# wifi-plug.net
KiCad netlist of a schematic drawn in Altium Designer
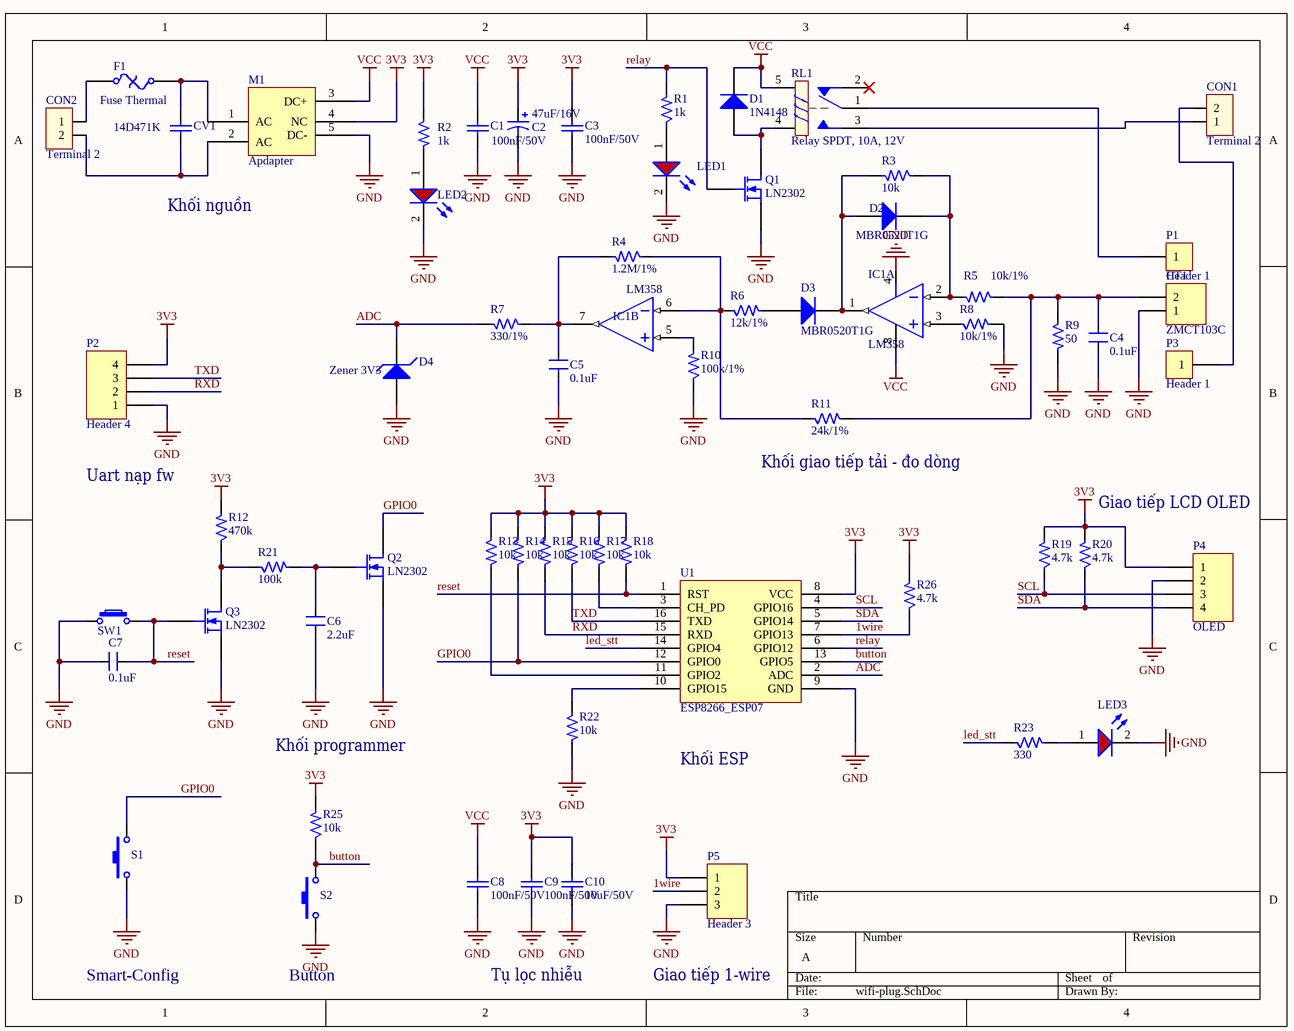
[diagram p0: wifi-plug.SchDoc]

(export (version "E")
  (design (tool "Eeschema 10.0.6"))
  (components
    (comp (ref "C1")
      (value "100nF/50V")
      (footprint "C0805")
      (description "Capacitor 100n 16V 0603")
      (fields (field (name "PUBLISHER") "Altium Limited"))
      (libsource (lib "Capacitor") (part "Cap Semi"))
    )
    (comp (ref "C2")
      (value "47uF/16V")
      (footprint "C2312")
      (description "Polarized Capacitor (Surface Mount)")
      (fields (field (name "PUBLISHER") "Altium Limited"))
      (libsource (lib "Miscellaneous Devices") (part "Cap Pol3"))
    )
    (comp (ref "C3")
      (value "100nF/50V")
      (footprint "C0805")
      (description "Capacitor 100n 16V 0603")
      (fields (field (name "PUBLISHER") "Altium Limited"))
      (libsource (lib "Capacitor") (part "Cap Semi"))
    )
    (comp (ref "C4")
      (value "0.1uF")
      (footprint "C0805")
      (description "SMD Ceramic  Capacitor")
      (fields (field (name "VOLTAGE") "50V") (field (name "TOLERANCE") "10%"))
      (libsource (lib "ST") (part "CM Ceramic"))
    )
    (comp (ref "C5")
      (value "0.1uF")
      (footprint "C0805")
      (description "SMD Ceramic  Capacitor")
      (fields (field (name "VOLTAGE") "50V") (field (name "TOLERANCE") "10%"))
      (libsource (lib "ST") (part "CM Ceramic"))
    )
    (comp (ref "C6")
      (value "2.2uF")
      (footprint "C0805")
      (description "SMD Ceramic  Capacitor")
      (fields (field (name "VOLTAGE") "50V") (field (name "TOLERANCE") "10%"))
      (libsource (lib "ST") (part "CM Ceramic"))
    )
    (comp (ref "C7")
      (value "0.1uF")
      (footprint "C0805")
      (description "SMD Ceramic  Capacitor")
      (fields (field (name "VOLTAGE") "50V") (field (name "TOLERANCE") "10%"))
      (libsource (lib "ST") (part "CM Ceramic"))
    )
    (comp (ref "C8")
      (value "100nF/50V")
      (footprint "C0805")
      (description "Capacitor 100n 16V 0603")
      (fields (field (name "PUBLISHER") "Altium Limited"))
      (libsource (lib "Capacitor") (part "Cap Semi"))
    )
    (comp (ref "C9")
      (value "100nF/50V")
      (footprint "C0805")
      (description "Capacitor 100n 16V 0603")
      (fields (field (name "PUBLISHER") "Altium Limited"))
      (libsource (lib "Capacitor") (part "Cap Semi"))
    )
    (comp (ref "C10")
      (value "10uF/50V")
      (footprint "C1206")
      (description "Capacitor 100n 16V 0603")
      (fields (field (name "PUBLISHER") "Altium Limited"))
      (libsource (lib "Capacitor") (part "Cap Semi"))
    )
    (comp (ref "CON1")
      (value "Terminal 2")
      (footprint "domino-2pin-7.62")
      (libsource (lib "") (part "Terminal 2_1"))
    )
    (comp (ref "CON2")
      (value "Terminal 2")
      (footprint "domino-2pin-7.62")
      (libsource (lib "SS_Con") (part "Terminal 2"))
    )
    (comp (ref "CT1")
      (value "ZMCT103C")
      (footprint "ZMCT103C")
      (description "Header, 2-Pin")
      (fields (field (name "PUBLISHER") "Altium Limited"))
      (libsource (lib "SS_Con") (part "Header 2"))
    )
    (comp (ref "CV1")
      (value "14D471K")
      (footprint "C_Ceramic_KV")
      (description "Polar Capacitor")
      (fields (field (name "Comment") "Cap1") (field (name "PUBLISHER") "Altium Limited"))
      (libsource (lib "SS_Basic") (part "Cap1"))
    )
    (comp (ref "D1")
      (value "1N4148")
      (footprint "DO-214AC (SMA)")
      (description "Diode Normal")
      (fields (field (name "PUBLISHER") "Altium Limited"))
      (libsource (lib "Schematic") (part "Diode Normal"))
    )
    (comp (ref "D2")
      (value "MBR0520T1G")
      (footprint "SOD-123 W")
      (description "Diode Normal")
      (fields (field (name "PUBLISHER") "Altium Limited"))
      (libsource (lib "Schematic") (part "Diode Normal"))
    )
    (comp (ref "D3")
      (value "MBR0520T1G")
      (footprint "SOD-123 W")
      (description "Diode Normal")
      (fields (field (name "PUBLISHER") "Altium Limited"))
      (libsource (lib "Schematic") (part "Diode Normal"))
    )
    (comp (ref "D4")
      (value "Zener 3V3")
      (footprint "SOD-123")
      (description "Zener Voltage Regulators")
      (fields (field (name "MANUFACTURER") "ON Semiconductor"))
      (libsource (lib "ST") (part "Diode Zener"))
    )
    (comp (ref "F1")
      (value "Fuse Thermal")
      (footprint "PTC1812")
      (description "Thermal Fuse")
      (fields (field (name "PUBLISHER") "Altium Limited"))
      (libsource (lib "Miscellaneous Devices") (part "Fuse Thermal"))
    )
    (comp (ref "IC1")
      (value "LM358")
      (footprint "SOIC8")
      (description "Low-Power Dual Operational Amplifier")
      (libsource (lib "ST") (part "LM358"))
    )
    (comp (ref "LED1")
      (value "150080RS75000")
      (footprint "led-3mm")
      (description "SMD mono-color Chip LED, WL-SMCW, Red")
      (fields
        (field (name "MANUFACTURER") "W黵th Elektronik eiSos GmbH")
        (field (name "CREATED BY") "Christin Otto")
      )
      (libsource (lib "led-lib") (part "led-0805"))
    )
    (comp (ref "LED2")
      (value "150080RS75000")
      (footprint "LED_0805_Red")
      (description "SMD mono-color Chip LED, WL-SMCW, Red")
      (fields
        (field (name "MANUFACTURER") "W黵th Elektronik eiSos GmbH")
        (field (name "CREATED BY") "Christin Otto")
      )
      (libsource (lib "led-lib") (part "led-0805"))
    )
    (comp (ref "LED3")
      (value "150080RS75000")
      (footprint "led-lib:led-3mm")
      (description "SMD mono-color Chip LED, WL-SMCW, Red")
      (fields
        (field (name "MANUFACTURER") "W黵th Elektronik eiSos GmbH")
        (field (name "CREATED BY") "Christin Otto")
      )
      (libsource (lib "led-lib") (part "led-0805"))
    )
    (comp (ref "M1")
      (value "Apdapter")
      (footprint "Module-Supply")
      (libsource (lib "SS_Module") (part "Module_Supply"))
    )
    (comp (ref "P1")
      (value "Header 1")
      (footprint "PAD 1")
      (description "Header, 1-Pin")
      (fields (field (name "PUBLISHER") "Altium Limited"))
      (libsource (lib "") (part "Header 1_1"))
    )
    (comp (ref "P2")
      (value "Header 4")
      (footprint "SS_Con:HDR1X4H")
      (description "Header, 4-Pin")
      (fields (field (name "PUBLISHER") "Altium Limited"))
      (libsource (lib "SS_Con") (part "Header 4"))
    )
    (comp (ref "P3")
      (value "Header 1")
      (footprint "PAD 1")
      (description "Header, 1-Pin")
      (fields (field (name "PUBLISHER") "Altium Limited"))
      (libsource (lib "SS_Con") (part "Header 1"))
    )
    (comp (ref "P4")
      (value "OLED")
      (footprint "SS_Con:HDR1X4 - FEMALE")
      (description "Header, 4-Pin")
      (fields (field (name "PUBLISHER") "Altium Limited"))
      (libsource (lib "") (part "Header 4_1"))
    )
    (comp (ref "P5")
      (value "Header 3")
      (footprint "SS_Con:HDR1X3")
      (description "Header, 3-Pin")
      (fields (field (name "PUBLISHER") "Altium Limited"))
      (libsource (lib "SS_Con") (part "Header 3"))
    )
    (comp (ref "Q1")
      (value "LN2302")
      (footprint "PcbLib1:SOT23-3")
      (description "N-Channel MOSFET")
      (fields (field (name "PUBLISHER") "Altium Limited"))
      (libsource (lib "Schlib2") (part "MOSFET-N"))
    )
    (comp (ref "Q2")
      (value "LN2302")
      (footprint "SOT23-3")
      (description "N-Channel MOSFET")
      (fields (field (name "PUBLISHER") "Altium Limited"))
      (libsource (lib "Schlib2") (part "MOSFET-N"))
    )
    (comp (ref "Q3")
      (value "LN2302")
      (footprint "SOT23-3")
      (description "N-Channel MOSFET")
      (fields (field (name "PUBLISHER") "Altium Limited"))
      (libsource (lib "Schlib2") (part "MOSFET-N"))
    )
    (comp (ref "R1")
      (value "1k")
      (footprint "R0805")
      (description "Resistor SMD")
      (fields (field (name "MANUFACTURER") "UniOhm"))
      (libsource (lib "ST") (part "RM"))
    )
    (comp (ref "R2")
      (value "1k")
      (footprint "R0805")
      (description "Resistor SMD")
      (fields (field (name "MANUFACTURER") "UniOhm"))
      (libsource (lib "ST") (part "RM"))
    )
    (comp (ref "R3")
      (value "10k")
      (footprint "R0805")
      (description "Resistor SMD")
      (fields (field (name "MANUFACTURER") "UniOhm"))
      (libsource (lib "ST") (part "RM"))
    )
    (comp (ref "R4")
      (value "1.2M/1%")
      (footprint "R0805")
      (description "Resistor SMD")
      (fields (field (name "MANUFACTURER") "UniOhm"))
      (libsource (lib "ST") (part "RM"))
    )
    (comp (ref "R5")
      (value "10k/1%")
      (footprint "R0805")
      (description "Resistor SMD")
      (fields (field (name "MANUFACTURER") "UniOhm"))
      (libsource (lib "ST") (part "RM"))
    )
    (comp (ref "R6")
      (value "12k/1%")
      (footprint "R0805")
      (description "Resistor SMD")
      (fields (field (name "MANUFACTURER") "UniOhm"))
      (libsource (lib "ST") (part "RM"))
    )
    (comp (ref "R7")
      (value "330/1%")
      (footprint "R0805")
      (description "Resistor SMD")
      (fields (field (name "MANUFACTURER") "UniOhm"))
      (libsource (lib "ST") (part "RM"))
    )
    (comp (ref "R8")
      (value "10k/1%")
      (footprint "R0805")
      (description "Resistor SMD")
      (fields (field (name "MANUFACTURER") "UniOhm"))
      (libsource (lib "ST") (part "RM"))
    )
    (comp (ref "R9")
      (value "50")
      (footprint "R0805")
      (description "Resistor SMD")
      (fields (field (name "MANUFACTURER") "UniOhm"))
      (libsource (lib "ST") (part "RM"))
    )
    (comp (ref "R10")
      (value "100k/1%")
      (footprint "R0805")
      (description "Resistor SMD")
      (fields (field (name "MANUFACTURER") "UniOhm"))
      (libsource (lib "ST") (part "RM"))
    )
    (comp (ref "R11")
      (value "24k/1%")
      (footprint "R0805")
      (description "Resistor SMD")
      (fields (field (name "MANUFACTURER") "UniOhm"))
      (libsource (lib "ST") (part "RM"))
    )
    (comp (ref "R12")
      (value "470k")
      (footprint "R0805")
      (description "Resistor SMD")
      (fields (field (name "MANUFACTURER") "UniOhm"))
      (libsource (lib "ST") (part "RM"))
    )
    (comp (ref "R13")
      (value "10k")
      (footprint "R0805")
      (description "Resistor SMD")
      (fields (field (name "MANUFACTURER") "UniOhm"))
      (libsource (lib "ST") (part "RM"))
    )
    (comp (ref "R14")
      (value "10k")
      (footprint "R0805")
      (description "Resistor SMD")
      (fields (field (name "MANUFACTURER") "UniOhm"))
      (libsource (lib "ST") (part "RM"))
    )
    (comp (ref "R15")
      (value "10k")
      (footprint "R0805")
      (description "Resistor SMD")
      (fields (field (name "MANUFACTURER") "UniOhm"))
      (libsource (lib "ST") (part "RM"))
    )
    (comp (ref "R16")
      (value "10k")
      (footprint "R0805")
      (description "Resistor SMD")
      (fields (field (name "MANUFACTURER") "UniOhm"))
      (libsource (lib "ST") (part "RM"))
    )
    (comp (ref "R17")
      (value "10k")
      (footprint "R0805")
      (description "Resistor SMD")
      (fields (field (name "MANUFACTURER") "UniOhm"))
      (libsource (lib "ST") (part "RM"))
    )
    (comp (ref "R18")
      (value "10k")
      (footprint "R0805")
      (description "Resistor SMD")
      (fields (field (name "MANUFACTURER") "UniOhm"))
      (libsource (lib "ST") (part "RM"))
    )
    (comp (ref "R19")
      (value "4.7k")
      (footprint "R0805")
      (description "Resistor SMD")
      (fields (field (name "MANUFACTURER") "UniOhm"))
      (libsource (lib "ST") (part "RM"))
    )
    (comp (ref "R20")
      (value "4.7k")
      (footprint "R0805")
      (description "Resistor SMD")
      (fields (field (name "MANUFACTURER") "UniOhm"))
      (libsource (lib "ST") (part "RM"))
    )
    (comp (ref "R21")
      (value "100k")
      (footprint "R0805")
      (description "Resistor SMD")
      (fields (field (name "MANUFACTURER") "UniOhm"))
      (libsource (lib "ST") (part "RM"))
    )
    (comp (ref "R22")
      (value "10k")
      (footprint "R0805")
      (description "Resistor SMD")
      (fields (field (name "MANUFACTURER") "UniOhm"))
      (libsource (lib "ST") (part "RM"))
    )
    (comp (ref "R23")
      (value "330")
      (footprint "R0805")
      (description "Resistor SMD")
      (fields (field (name "MANUFACTURER") "UniOhm"))
      (libsource (lib "ST") (part "RM"))
    )
    (comp (ref "R25")
      (value "10k")
      (footprint "R0805")
      (description "Resistor SMD")
      (fields (field (name "MANUFACTURER") "UniOhm"))
      (libsource (lib "ST") (part "RM"))
    )
    (comp (ref "R26")
      (value "4.7k")
      (footprint "R0805")
      (description "Resistor SMD")
      (fields (field (name "MANUFACTURER") "UniOhm"))
      (libsource (lib "ST") (part "RM"))
    )
    (comp (ref "RL1")
      (value "Relay SPDT, 10A, 12V")
      (footprint "RL_SPDT_10A")
      (description "Relay SPDT,10A - 12VDC 5 Pin")
      (libsource (lib "nhantt-relay-lib") (part "Relay 1"))
    )
    (comp (ref "S1")
      (value "SW-SMD")
      (footprint "Button Tactile Switch")
      (description "Switch")
      (fields (field (name "PUBLISHER") "Altium Limited"))
      (libsource (lib "Schematic") (part "SW-SMD"))
    )
    (comp (ref "S2")
      (value "SW-SMD")
      (footprint "Button Tactile Switch")
      (description "Switch")
      (fields (field (name "PUBLISHER") "Altium Limited"))
      (libsource (lib "Schematic") (part "SW-SMD"))
    )
    (comp (ref "SW1") (value "SW2") (footprint "SMD(2)") (libsource (lib "SC") (part "SW2")))
    (comp (ref "U1")
      (value "ESP8266_ESP07")
      (footprint "ESP_12")
      (libsource (lib "STMicroelectronics") (part "ESP8266_ESP07"))
    )
  )
  (nets
    (net (code "1") (name "/1wire") (class "Default")
      (node (ref "P5") (pin "2") (pinfunction "2_2") (pintype "passive"))
      (node (ref "R26") (pin "1") (pinfunction "1_1") (pintype "passive"))
      (node (ref "U1") (pin "7") (pinfunction "GPIO13_7") (pintype "passive"))
    )
    (net (code "2") (name "/ADC") (class "Default")
      (node (ref "D4") (pin "1") (pinfunction "K_1") (pintype "passive"))
      (node (ref "R7") (pin "2") (pinfunction "2_2") (pintype "passive"))
      (node (ref "U1") (pin "2") (pinfunction "ADC_2") (pintype "passive"))
    )
    (net (code "3") (name "/GPIO0") (class "Default")
      (node (ref "Q2") (pin "3") (pinfunction "D_3") (pintype "passive"))
      (node (ref "R14") (pin "2") (pinfunction "2_2") (pintype "passive"))
      (node (ref "S1") (pin "2") (pinfunction "2_2") (pintype "passive"))
      (node (ref "U1") (pin "12") (pinfunction "GPIO0_12") (pintype "passive"))
    )
    (net (code "4") (name "/RXD") (class "Default")
      (node (ref "P2") (pin "2") (pinfunction "2_2") (pintype "passive"))
      (node (ref "R15") (pin "2") (pinfunction "2_2") (pintype "passive"))
      (node (ref "U1") (pin "15") (pinfunction "RXD_15") (pintype "passive"))
    )
    (net (code "5") (name "/SCL") (class "Default")
      (node (ref "P4") (pin "3") (pinfunction "3_3") (pintype "passive"))
      (node (ref "R19") (pin "1") (pinfunction "1_1") (pintype "passive"))
      (node (ref "U1") (pin "4") (pinfunction "GPIO16_4") (pintype "passive"))
    )
    (net (code "6") (name "/SDA") (class "Default")
      (node (ref "P4") (pin "4") (pinfunction "4_4") (pintype "passive"))
      (node (ref "R20") (pin "1") (pinfunction "1_1") (pintype "passive"))
      (node (ref "U1") (pin "5") (pinfunction "GPIO14_5") (pintype "passive"))
    )
    (net (code "7") (name "/TXD") (class "Default")
      (node (ref "P2") (pin "3") (pinfunction "3_3") (pintype "passive"))
      (node (ref "R16") (pin "2") (pinfunction "2_2") (pintype "passive"))
      (node (ref "U1") (pin "16") (pinfunction "TXD_16") (pintype "passive"))
    )
    (net (code "8") (name "/button") (class "Default")
      (node (ref "R25") (pin "1") (pinfunction "1_1") (pintype "passive"))
      (node (ref "S2") (pin "2") (pinfunction "2_2") (pintype "passive"))
      (node (ref "U1") (pin "13") (pinfunction "GPIO5_13") (pintype "passive"))
    )
    (net (code "9") (name "/led_stt") (class "Default")
      (node (ref "R23") (pin "1") (pinfunction "1_1") (pintype "passive"))
      (node (ref "U1") (pin "14") (pinfunction "GPIO4_14") (pintype "passive"))
    )
    (net (code "10") (name "/relay") (class "Default")
      (node (ref "Q1") (pin "1") (pinfunction "G_1") (pintype "passive"))
      (node (ref "R1") (pin "2") (pinfunction "2_2") (pintype "passive"))
      (node (ref "U1") (pin "6") (pinfunction "GPIO12_6") (pintype "passive"))
    )
    (net (code "11") (name "/reset") (class "Default")
      (node (ref "C7") (pin "2") (pinfunction "2_2") (pintype "passive"))
      (node (ref "Q3") (pin "1") (pinfunction "G_1") (pintype "passive"))
      (node (ref "R18") (pin "2") (pinfunction "2_2") (pintype "passive"))
      (node (ref "SW1") (pin "2") (pinfunction "2_2") (pintype "passive"))
      (node (ref "U1") (pin "1") (pinfunction "RST_1") (pintype "passive"))
    )
    (net (code "12") (name "3V3") (class "Default")
      (node (ref "C10") (pin "1") (pinfunction "1_1") (pintype "passive"))
      (node (ref "C2") (pin "1") (pinfunction "1_1") (pintype "passive"))
      (node (ref "C3") (pin "1") (pinfunction "1_1") (pintype "passive"))
      (node (ref "C9") (pin "1") (pinfunction "1_1") (pintype "passive"))
      (node (ref "M1") (pin "4") (pinfunction "NC_4") (pintype "passive"))
      (node (ref "P2") (pin "4") (pinfunction "4_4") (pintype "passive"))
      (node (ref "P4") (pin "1") (pinfunction "1_1") (pintype "passive"))
      (node (ref "P5") (pin "1") (pinfunction "1_1") (pintype "passive"))
      (node (ref "R12") (pin "2") (pinfunction "2_2") (pintype "passive"))
      (node (ref "R13") (pin "1") (pinfunction "1_1") (pintype "passive"))
      (node (ref "R14") (pin "1") (pinfunction "1_1") (pintype "passive"))
      (node (ref "R15") (pin "1") (pinfunction "1_1") (pintype "passive"))
      (node (ref "R16") (pin "1") (pinfunction "1_1") (pintype "passive"))
      (node (ref "R17") (pin "1") (pinfunction "1_1") (pintype "passive"))
      (node (ref "R18") (pin "1") (pinfunction "1_1") (pintype "passive"))
      (node (ref "R19") (pin "2") (pinfunction "2_2") (pintype "passive"))
      (node (ref "R2") (pin "1") (pinfunction "1_1") (pintype "passive"))
      (node (ref "R20") (pin "2") (pinfunction "2_2") (pintype "passive"))
      (node (ref "R25") (pin "2") (pinfunction "2_2") (pintype "passive"))
      (node (ref "R26") (pin "2") (pinfunction "2_2") (pintype "passive"))
      (node (ref "U1") (pin "8") (pinfunction "VCC_8") (pintype "passive"))
    )
    (net (code "13") (name "GND") (class "Default")
      (node (ref "C1") (pin "2") (pinfunction "2_2") (pintype "passive"))
      (node (ref "C10") (pin "2") (pinfunction "2_2") (pintype "passive"))
      (node (ref "C2") (pin "2") (pinfunction "2_2") (pintype "passive"))
      (node (ref "C3") (pin "2") (pinfunction "2_2") (pintype "passive"))
      (node (ref "C4") (pin "1") (pinfunction "1_1") (pintype "passive"))
      (node (ref "C5") (pin "1") (pinfunction "1_1") (pintype "passive"))
      (node (ref "C6") (pin "1") (pinfunction "1_1") (pintype "passive"))
      (node (ref "C7") (pin "1") (pinfunction "1_1") (pintype "passive"))
      (node (ref "C8") (pin "2") (pinfunction "2_2") (pintype "passive"))
      (node (ref "C9") (pin "2") (pinfunction "2_2") (pintype "passive"))
      (node (ref "CT1") (pin "1") (pinfunction "1_1") (pintype "passive"))
      (node (ref "D4") (pin "2") (pinfunction "A_2") (pintype "passive"))
      (node (ref "IC1") (pin "4") (pinfunction "-V_4") (pintype "passive"))
      (node (ref "LED1") (pin "2") (pinfunction "C_2") (pintype "passive"))
      (node (ref "LED2") (pin "2") (pinfunction "C_2") (pintype "passive"))
      (node (ref "LED3") (pin "2") (pinfunction "C_2") (pintype "passive"))
      (node (ref "M1") (pin "5") (pinfunction "DC-_5") (pintype "passive"))
      (node (ref "P2") (pin "1") (pinfunction "1_1") (pintype "passive"))
      (node (ref "P4") (pin "2") (pinfunction "2_2") (pintype "passive"))
      (node (ref "P5") (pin "3") (pinfunction "3_3") (pintype "passive"))
      (node (ref "Q1") (pin "2") (pinfunction "S_2") (pintype "passive"))
      (node (ref "Q2") (pin "2") (pinfunction "S_2") (pintype "passive"))
      (node (ref "Q3") (pin "2") (pinfunction "S_2") (pintype "passive"))
      (node (ref "R10") (pin "1") (pinfunction "1_1") (pintype "passive"))
      (node (ref "R22") (pin "2") (pinfunction "2_2") (pintype "passive"))
      (node (ref "R8") (pin "2") (pinfunction "2_2") (pintype "passive"))
      (node (ref "R9") (pin "2") (pinfunction "2_2") (pintype "passive"))
      (node (ref "S1") (pin "1") (pinfunction "1_1") (pintype "passive"))
      (node (ref "S2") (pin "1") (pinfunction "1_1") (pintype "passive"))
      (node (ref "SW1") (pin "1") (pinfunction "1_1") (pintype "passive"))
      (node (ref "U1") (pin "9") (pinfunction "GND_9") (pintype "passive"))
    )
    (net (code "14") (name "Net-(C4-Pad2)") (class "Default")
      (node (ref "C4") (pin "2") (pinfunction "2_2") (pintype "passive"))
      (node (ref "CT1") (pin "2") (pinfunction "2_2") (pintype "passive"))
      (node (ref "R11") (pin "2") (pinfunction "2_2") (pintype "passive"))
      (node (ref "R5") (pin "1") (pinfunction "1_1") (pintype "passive"))
      (node (ref "R9") (pin "1") (pinfunction "1_1") (pintype "passive"))
    )
    (net (code "15") (name "Net-(CON1-Pad1)") (class "Default")
      (node (ref "CON1") (pin "1") (pinfunction "1_1") (pintype "passive"))
      (node (ref "RL1") (pin "3") (pinfunction "3_3") (pintype "passive"))
    )
    (net (code "16") (name "Net-(CON1-Pad2)") (class "Default")
      (node (ref "CON1") (pin "2") (pinfunction "2_2") (pintype "passive"))
      (node (ref "P3") (pin "1") (pinfunction "1_1") (pintype "passive"))
    )
    (net (code "17") (name "Net-(CON2-Pad1)") (class "Default")
      (node (ref "CON2") (pin "1") (pinfunction "1_1") (pintype "passive"))
      (node (ref "F1") (pin "1") (pinfunction "1_1") (pintype "passive"))
    )
    (net (code "18") (name "Net-(CON2-Pad2)") (class "Default")
      (node (ref "CON2") (pin "2") (pinfunction "2_2") (pintype "passive"))
      (node (ref "CV1") (pin "1") (pinfunction "1_1") (pintype "passive"))
      (node (ref "M1") (pin "2") (pinfunction "AC_2") (pintype "passive"))
    )
    (net (code "19") (name "Net-(CV1-Pad2)") (class "Default")
      (node (ref "CV1") (pin "2") (pinfunction "2_2") (pintype "passive"))
      (node (ref "F1") (pin "2") (pinfunction "2_2") (pintype "passive"))
      (node (ref "M1") (pin "1") (pinfunction "AC_1") (pintype "passive"))
    )
    (net (code "20") (name "Net-(D1-A)") (class "Default")
      (node (ref "D1") (pin "1") (pinfunction "A_1") (pintype "passive"))
      (node (ref "Q1") (pin "3") (pinfunction "D_3") (pintype "passive"))
      (node (ref "RL1") (pin "4") (pinfunction "4_4") (pintype "passive"))
    )
    (net (code "21") (name "Net-(D2-A)") (class "Default")
      (node (ref "D2") (pin "1") (pinfunction "A_1") (pintype "passive"))
      (node (ref "D3") (pin "2") (pinfunction "K_2") (pintype "passive"))
      (node (ref "IC1") (pin "1") (pinfunction "OUT_1") (pintype "output"))
      (node (ref "R3") (pin "2") (pinfunction "2_2") (pintype "passive"))
    )
    (net (code "22") (name "Net-(D2-K)") (class "Default")
      (node (ref "D2") (pin "2") (pinfunction "K_2") (pintype "passive"))
      (node (ref "IC1") (pin "2") (pinfunction "IN-_2") (pintype "input"))
      (node (ref "R3") (pin "1") (pinfunction "1_1") (pintype "passive"))
      (node (ref "R5") (pin "2") (pinfunction "2_2") (pintype "passive"))
    )
    (net (code "23") (name "Net-(D3-A)") (class "Default")
      (node (ref "D3") (pin "1") (pinfunction "A_1") (pintype "passive"))
      (node (ref "R6") (pin "2") (pinfunction "2_2") (pintype "passive"))
    )
    (net (code "24") (name "Net-(IC1A-IN+)") (class "Default")
      (node (ref "IC1") (pin "3") (pinfunction "IN+_3") (pintype "input"))
      (node (ref "R8") (pin "1") (pinfunction "1_1") (pintype "passive"))
    )
    (net (code "25") (name "Net-(IC1B-IN+)") (class "Default")
      (node (ref "IC1") (pin "5") (pinfunction "IN+_5") (pintype "input"))
      (node (ref "R10") (pin "2") (pinfunction "2_2") (pintype "passive"))
    )
    (net (code "26") (name "Net-(IC1B-IN-)") (class "Default")
      (node (ref "IC1") (pin "6") (pinfunction "IN-_6") (pintype "input"))
      (node (ref "R11") (pin "1") (pinfunction "1_1") (pintype "passive"))
      (node (ref "R4") (pin "1") (pinfunction "1_1") (pintype "passive"))
      (node (ref "R6") (pin "1") (pinfunction "1_1") (pintype "passive"))
    )
    (net (code "27") (name "Net-(IC1B-OUT)") (class "Default")
      (node (ref "C5") (pin "2") (pinfunction "2_2") (pintype "passive"))
      (node (ref "IC1") (pin "7") (pinfunction "OUT_7") (pintype "output"))
      (node (ref "R4") (pin "2") (pinfunction "2_2") (pintype "passive"))
      (node (ref "R7") (pin "1") (pinfunction "1_1") (pintype "passive"))
    )
    (net (code "28") (name "Net-(LED1-A)") (class "Default")
      (node (ref "LED1") (pin "1") (pinfunction "A_1") (pintype "passive"))
      (node (ref "R1") (pin "1") (pinfunction "1_1") (pintype "passive"))
    )
    (net (code "29") (name "Net-(LED2-A)") (class "Default")
      (node (ref "LED2") (pin "1") (pinfunction "A_1") (pintype "passive"))
      (node (ref "R2") (pin "2") (pinfunction "2_2") (pintype "passive"))
    )
    (net (code "30") (name "Net-(LED3-A)") (class "Default")
      (node (ref "LED3") (pin "1") (pinfunction "A_1") (pintype "passive"))
      (node (ref "R23") (pin "2") (pinfunction "2_2") (pintype "passive"))
    )
    (net (code "31") (name "Net-(P1-Pad1)") (class "Default")
      (node (ref "P1") (pin "1") (pinfunction "1_1") (pintype "passive"))
      (node (ref "RL1") (pin "1") (pinfunction "1_1") (pintype "passive"))
    )
    (net (code "32") (name "Net-(Q2-G)") (class "Default")
      (node (ref "C6") (pin "2") (pinfunction "2_2") (pintype "passive"))
      (node (ref "Q2") (pin "1") (pinfunction "G_1") (pintype "passive"))
      (node (ref "R21") (pin "2") (pinfunction "2_2") (pintype "passive"))
    )
    (net (code "33") (name "Net-(Q3-D)") (class "Default")
      (node (ref "Q3") (pin "3") (pinfunction "D_3") (pintype "passive"))
      (node (ref "R12") (pin "1") (pinfunction "1_1") (pintype "passive"))
      (node (ref "R21") (pin "1") (pinfunction "1_1") (pintype "passive"))
    )
    (net (code "34") (name "Net-(U1-CH_PD)") (class "Default")
      (node (ref "R17") (pin "2") (pinfunction "2_2") (pintype "passive"))
      (node (ref "U1") (pin "3") (pinfunction "CH_PD_3") (pintype "passive"))
    )
    (net (code "35") (name "Net-(U1-GPIO2)") (class "Default")
      (node (ref "R13") (pin "2") (pinfunction "2_2") (pintype "passive"))
      (node (ref "U1") (pin "11") (pinfunction "GPIO2_11") (pintype "passive"))
    )
    (net (code "36") (name "Net-(U1-GPIO15)") (class "Default")
      (node (ref "R22") (pin "1") (pinfunction "1_1") (pintype "passive"))
      (node (ref "U1") (pin "10") (pinfunction "GPIO15_10") (pintype "passive"))
    )
    (net (code "37") (name "VCC") (class "Default")
      (node (ref "C1") (pin "1") (pinfunction "1_1") (pintype "passive"))
      (node (ref "C8") (pin "1") (pinfunction "1_1") (pintype "passive"))
      (node (ref "D1") (pin "2") (pinfunction "K_2") (pintype "passive"))
      (node (ref "IC1") (pin "8") (pinfunction "+V_8") (pintype "passive"))
      (node (ref "M1") (pin "3") (pinfunction "DC+_3") (pintype "passive"))
      (node (ref "RL1") (pin "5") (pinfunction "5_5") (pintype "passive"))
    )
    (net (code "38") (name "unconnected-(RL1-Pad2)") (class "Default")
      (node (ref "RL1") (pin "2") (pinfunction "2_2") (pintype "passive+no_connect"))
    )
  )
)
